# Escorna_CPU_1_01.net
KiCad netlist of a schematic drawn in EAGLE
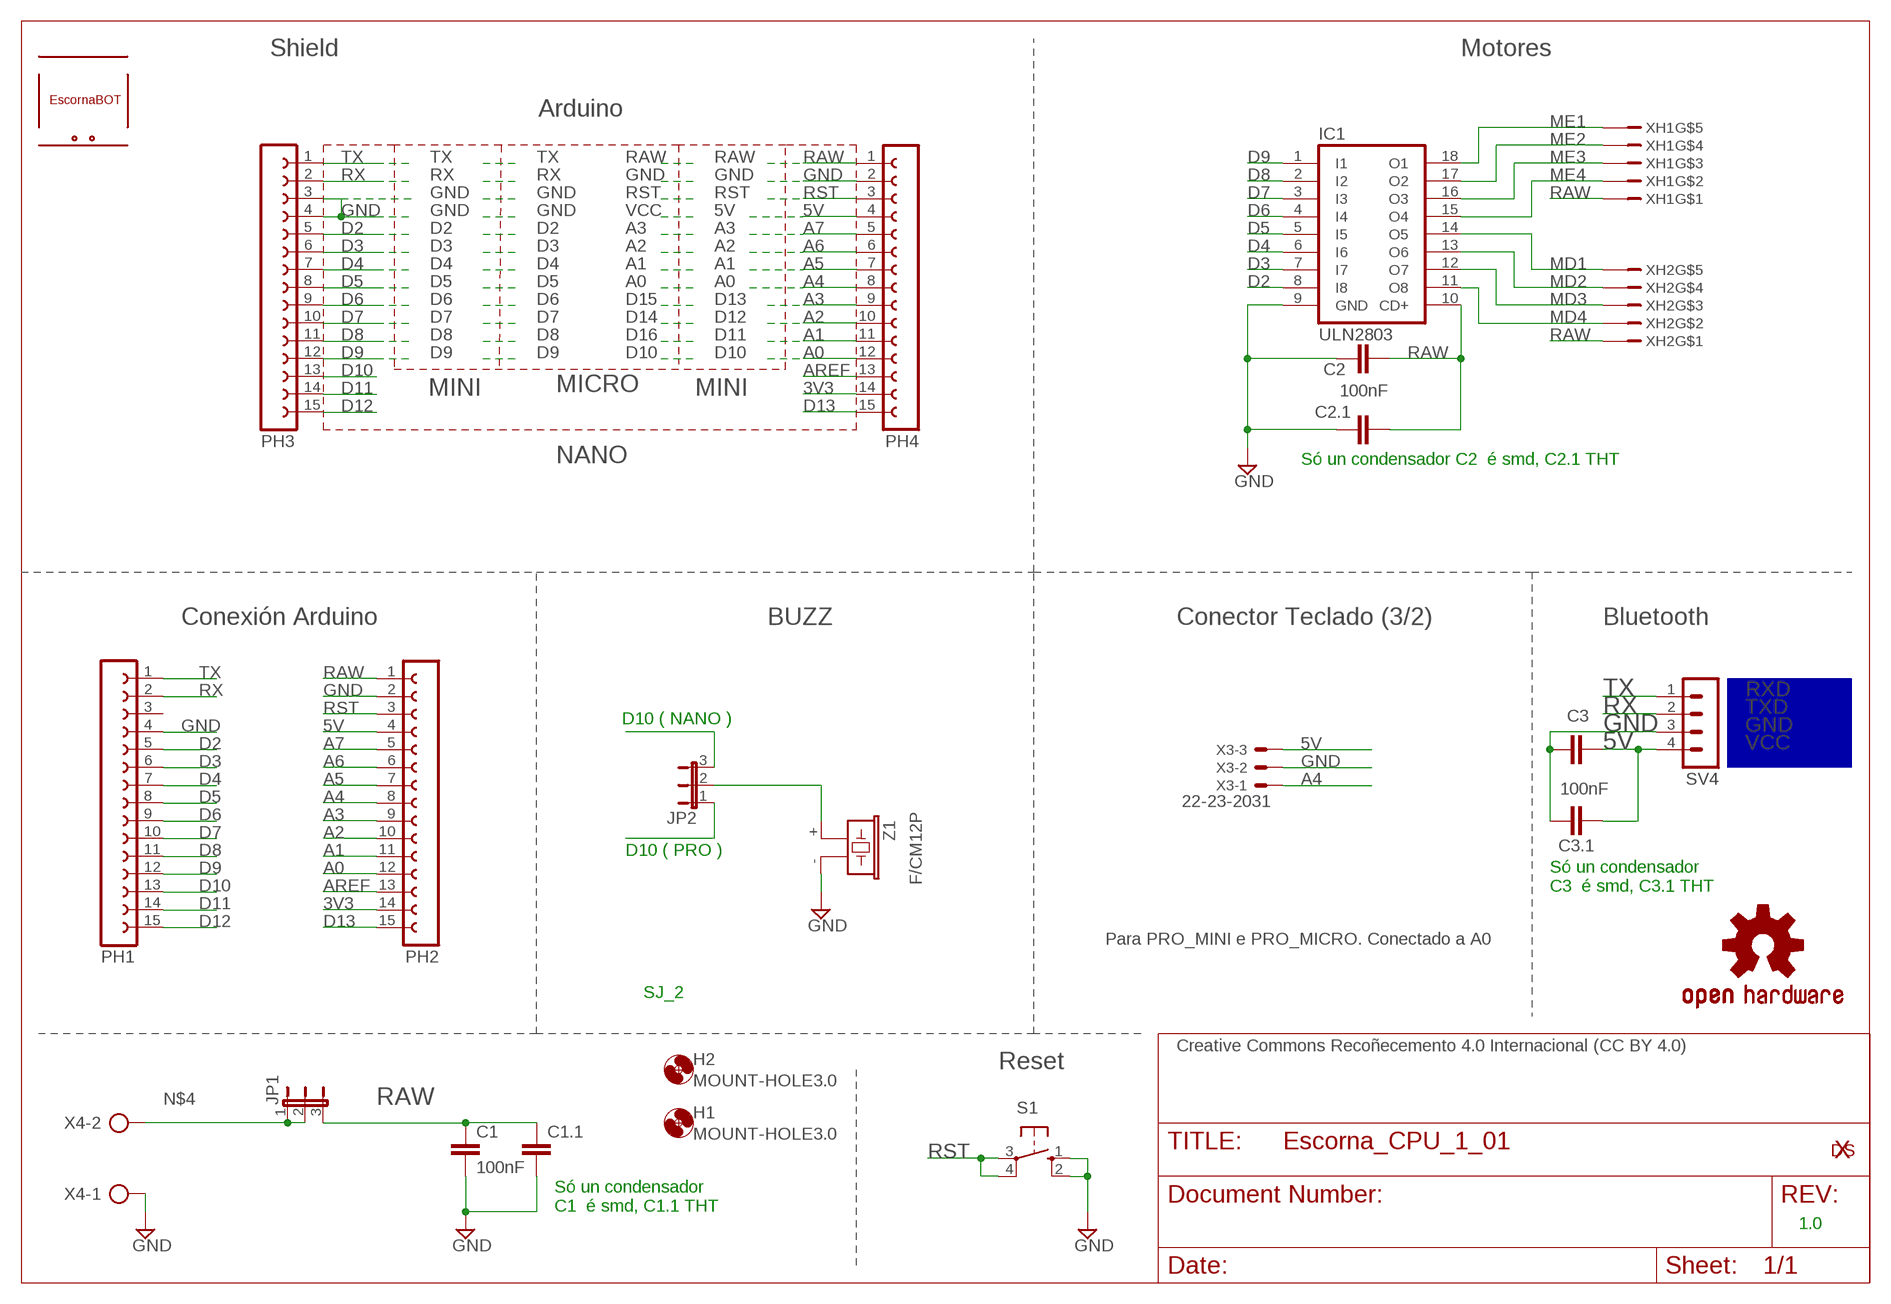
[diagram p0: schematic, sheet 1]

(export (version "E")
  (design (tool "Eeschema 10.0.6"))
  (components
    (comp (ref "C1")
      (value "100nF")
      (footprint "eagle-import:C1206")
      (libsource (lib "eagle-import") (part "C-EUC1206"))
    )
    (comp (ref "C1.1")
      (value "C-EU025-024X044")
      (footprint "eagle-import:C025-024X044")
      (libsource (lib "eagle-import") (part "C-EU025-024X044"))
    )
    (comp (ref "C2")
      (value "100nF")
      (footprint "eagle-import:C1206")
      (libsource (lib "eagle-import") (part "C-EUC1206"))
    )
    (comp (ref "C2.1")
      (value "C-EU025-024X044")
      (footprint "eagle-import:C025-024X044")
      (libsource (lib "eagle-import") (part "C-EU025-024X044"))
    )
    (comp (ref "C3")
      (value "100nF")
      (footprint "eagle-import:C1206")
      (libsource (lib "eagle-import") (part "C-EUC1206"))
    )
    (comp (ref "C3.1")
      (value "C-EU025-024X044")
      (footprint "eagle-import:C025-024X044")
      (libsource (lib "eagle-import") (part "C-EU025-024X044"))
    )
    (comp (ref "H1")
      (value "MOUNT-HOLE3.0")
      (footprint "eagle-import:3,0")
      (libsource (lib "eagle-import") (part "MOUNT-HOLE3.0"))
    )
    (comp (ref "H2")
      (value "MOUNT-HOLE3.0")
      (footprint "eagle-import:3,0")
      (libsource (lib "eagle-import") (part "MOUNT-HOLE3.0"))
    )
    (comp (ref "IC1")
      (value "ULN2803")
      (footprint "eagle-import:DIL18")
      (libsource (lib "eagle-import") (part "ULN2803A{dblquote}"))
    )
    (comp (ref "JP1")
      (value "JP2E")
      (footprint "eagle-import:JP2")
      (libsource (lib "eagle-import") (part "JP2E"))
    )
    (comp (ref "JP2")
      (value "JP2E")
      (footprint "eagle-import:JP2")
      (libsource (lib "eagle-import") (part "JP2E"))
    )
    (comp (ref "LOGO1")
      (value "OSHW-LOGOS")
      (footprint "eagle-import:OSHW-LOGO-S")
      (libsource (lib "eagle-import") (part "OSHW-LOGOS"))
    )
    (comp (ref "PH1")
      (value "FE15-1")
      (footprint "eagle-import:FE15")
      (libsource (lib "eagle-import") (part "FE15-1"))
    )
    (comp (ref "PH2")
      (value "FE15-1")
      (footprint "eagle-import:FE15")
      (libsource (lib "eagle-import") (part "FE15-1"))
    )
    (comp (ref "PH3")
      (value "FE15-1")
      (footprint "eagle-import:FE15")
      (libsource (lib "eagle-import") (part "FE15-1"))
    )
    (comp (ref "PH4")
      (value "FE15-1")
      (footprint "eagle-import:FE15")
      (libsource (lib "eagle-import") (part "FE15-1"))
    )
    (comp (ref "S1")
      (value "10-XX")
      (footprint "eagle-import:B3F-10XX")
      (fields (field (name "MPN") "B3F-1000"))
      (libsource (lib "eagle-import") (part "10-XX"))
    )
    (comp (ref "SV4")
      (value "MA04-1")
      (footprint "eagle-import:MA04-1")
      (libsource (lib "eagle-import") (part "MA04-1"))
    )
    (comp (ref "U$1")
      (value "ESCORNABOT")
      (footprint "eagle-import:ESCORNA_PEQUE")
      (libsource (lib "eagle-import") (part "ESCORNABOT"))
    )
    (comp (ref "U$6")
      (value "XDESIG")
      (footprint "eagle-import:XDESIG_CU")
      (libsource (lib "eagle-import") (part "XDESIG"))
    )
    (comp (ref "X3")
      (value "22-23-2031")
      (footprint "eagle-import:22-23-2031")
      (fields (field (name "MF") "MOLEX"))
      (libsource (lib "eagle-import") (part "22-23-2031"))
    )
    (comp (ref "X4")
      (value "AK500/2")
      (footprint "eagle-import:AK500_2")
      (libsource (lib "eagle-import") (part "AK500/2"))
    )
    (comp (ref "XH1")
      (value "B5B-XH-A")
      (footprint "eagle-import:B5B-XH-A")
      (libsource (lib "eagle-import") (part "B5B-XH-A"))
    )
    (comp (ref "XH2")
      (value "B5B-XH-A")
      (footprint "eagle-import:B5B-XH-A")
      (libsource (lib "eagle-import") (part "B5B-XH-A"))
    )
    (comp (ref "Z1")
      (value "F/CM12P")
      (footprint "eagle-import:F_CM12P")
      (libsource (lib "eagle-import") (part "F/CM12P"))
    )
  )
  (nets
    (net (code "1") (name "/3V3") (class "Default")
      (node (ref "PH2") (pin "14") (pinfunction "14_14") (pintype "passive"))
      (node (ref "PH4") (pin "14") (pinfunction "14_14") (pintype "passive"))
    )
    (net (code "2") (name "/5V") (class "Default")
      (node (ref "C3") (pin "2") (pinfunction "2_2") (pintype "passive"))
      (node (ref "C3.1") (pin "2") (pinfunction "2_2") (pintype "passive"))
      (node (ref "PH2") (pin "4") (pinfunction "4_4") (pintype "passive"))
      (node (ref "PH4") (pin "4") (pinfunction "4_4") (pintype "passive"))
      (node (ref "SV4") (pin "4") (pinfunction "4_4") (pintype "passive"))
      (node (ref "X3") (pin "3") (pinfunction "S_3") (pintype "passive"))
    )
    (net (code "3") (name "/A0") (class "Default")
      (node (ref "JP2") (pin "1") (pinfunction "1_1") (pintype "passive"))
      (node (ref "PH2") (pin "12") (pinfunction "12_12") (pintype "passive"))
      (node (ref "PH4") (pin "12") (pinfunction "12_12") (pintype "passive"))
    )
    (net (code "4") (name "/A1") (class "Default")
      (node (ref "PH2") (pin "11") (pinfunction "11_11") (pintype "passive"))
      (node (ref "PH4") (pin "11") (pinfunction "11_11") (pintype "passive"))
    )
    (net (code "5") (name "/A2") (class "Default")
      (node (ref "PH2") (pin "10") (pinfunction "10_10") (pintype "passive"))
      (node (ref "PH4") (pin "10") (pinfunction "10_10") (pintype "passive"))
    )
    (net (code "6") (name "/A3") (class "Default")
      (node (ref "PH2") (pin "9") (pinfunction "9_9") (pintype "passive"))
      (node (ref "PH4") (pin "9") (pinfunction "9_9") (pintype "passive"))
    )
    (net (code "7") (name "/A4") (class "Default")
      (node (ref "PH2") (pin "8") (pinfunction "8_8") (pintype "passive"))
      (node (ref "PH4") (pin "8") (pinfunction "8_8") (pintype "passive"))
      (node (ref "X3") (pin "1") (pinfunction "S_1") (pintype "passive"))
    )
    (net (code "8") (name "/A5") (class "Default")
      (node (ref "PH2") (pin "7") (pinfunction "7_7") (pintype "passive"))
      (node (ref "PH4") (pin "7") (pinfunction "7_7") (pintype "passive"))
    )
    (net (code "9") (name "/A6") (class "Default")
      (node (ref "PH2") (pin "6") (pinfunction "6_6") (pintype "passive"))
      (node (ref "PH4") (pin "6") (pinfunction "6_6") (pintype "passive"))
    )
    (net (code "10") (name "/A7") (class "Default")
      (node (ref "PH2") (pin "5") (pinfunction "5_5") (pintype "passive"))
      (node (ref "PH4") (pin "5") (pinfunction "5_5") (pintype "passive"))
    )
    (net (code "11") (name "/AREF") (class "Default")
      (node (ref "PH2") (pin "13") (pinfunction "13_13") (pintype "passive"))
      (node (ref "PH4") (pin "13") (pinfunction "13_13") (pintype "passive"))
    )
    (net (code "12") (name "/D2") (class "Default")
      (node (ref "IC1") (pin "8") (pinfunction "I8_8") (pintype "input"))
      (node (ref "PH1") (pin "5") (pinfunction "5_5") (pintype "passive"))
      (node (ref "PH3") (pin "5") (pinfunction "5_5") (pintype "passive"))
    )
    (net (code "13") (name "/D3") (class "Default")
      (node (ref "IC1") (pin "7") (pinfunction "I7_7") (pintype "input"))
      (node (ref "PH1") (pin "6") (pinfunction "6_6") (pintype "passive"))
      (node (ref "PH3") (pin "6") (pinfunction "6_6") (pintype "passive"))
    )
    (net (code "14") (name "/D4") (class "Default")
      (node (ref "IC1") (pin "6") (pinfunction "I6_6") (pintype "input"))
      (node (ref "PH1") (pin "7") (pinfunction "7_7") (pintype "passive"))
      (node (ref "PH3") (pin "7") (pinfunction "7_7") (pintype "passive"))
    )
    (net (code "15") (name "/D5") (class "Default")
      (node (ref "IC1") (pin "5") (pinfunction "I5_5") (pintype "input"))
      (node (ref "PH1") (pin "8") (pinfunction "8_8") (pintype "passive"))
      (node (ref "PH3") (pin "8") (pinfunction "8_8") (pintype "passive"))
    )
    (net (code "16") (name "/D6") (class "Default")
      (node (ref "IC1") (pin "4") (pinfunction "I4_4") (pintype "input"))
      (node (ref "PH1") (pin "9") (pinfunction "9_9") (pintype "passive"))
      (node (ref "PH3") (pin "9") (pinfunction "9_9") (pintype "passive"))
    )
    (net (code "17") (name "/D7") (class "Default")
      (node (ref "IC1") (pin "3") (pinfunction "I3_3") (pintype "input"))
      (node (ref "PH1") (pin "10") (pinfunction "10_10") (pintype "passive"))
      (node (ref "PH3") (pin "10") (pinfunction "10_10") (pintype "passive"))
    )
    (net (code "18") (name "/D8") (class "Default")
      (node (ref "IC1") (pin "2") (pinfunction "I2_2") (pintype "input"))
      (node (ref "PH1") (pin "11") (pinfunction "11_11") (pintype "passive"))
      (node (ref "PH3") (pin "11") (pinfunction "11_11") (pintype "passive"))
    )
    (net (code "19") (name "/D9") (class "Default")
      (node (ref "IC1") (pin "1") (pinfunction "I1_1") (pintype "input"))
      (node (ref "PH1") (pin "12") (pinfunction "12_12") (pintype "passive"))
      (node (ref "PH3") (pin "12") (pinfunction "12_12") (pintype "passive"))
    )
    (net (code "20") (name "/D10") (class "Default")
      (node (ref "JP2") (pin "3") (pinfunction "3_3") (pintype "passive"))
      (node (ref "PH1") (pin "13") (pinfunction "13_13") (pintype "passive"))
      (node (ref "PH3") (pin "13") (pinfunction "13_13") (pintype "passive"))
    )
    (net (code "21") (name "/D11") (class "Default")
      (node (ref "PH1") (pin "14") (pinfunction "14_14") (pintype "passive"))
      (node (ref "PH3") (pin "14") (pinfunction "14_14") (pintype "passive"))
    )
    (net (code "22") (name "/D12") (class "Default")
      (node (ref "PH1") (pin "15") (pinfunction "15_15") (pintype "passive"))
      (node (ref "PH3") (pin "15") (pinfunction "15_15") (pintype "passive"))
    )
    (net (code "23") (name "/D13") (class "Default")
      (node (ref "PH2") (pin "15") (pinfunction "15_15") (pintype "passive"))
      (node (ref "PH4") (pin "15") (pinfunction "15_15") (pintype "passive"))
    )
    (net (code "24") (name "/MD1") (class "Default")
      (node (ref "IC1") (pin "14") (pinfunction "O5_14") (pintype "open_collector"))
      (node (ref "XH2") (pin "P$5") (pinfunction "1_P$5") (pintype "passive"))
    )
    (net (code "25") (name "/MD2") (class "Default")
      (node (ref "IC1") (pin "13") (pinfunction "O6_13") (pintype "open_collector"))
      (node (ref "XH2") (pin "P$4") (pinfunction "1_P$4") (pintype "passive"))
    )
    (net (code "26") (name "/MD3") (class "Default")
      (node (ref "IC1") (pin "12") (pinfunction "O7_12") (pintype "open_collector"))
      (node (ref "XH2") (pin "P$3") (pinfunction "1_P$3") (pintype "passive"))
    )
    (net (code "27") (name "/MD4") (class "Default")
      (node (ref "IC1") (pin "11") (pinfunction "O8_11") (pintype "open_collector"))
      (node (ref "XH2") (pin "P$2") (pinfunction "1_P$2") (pintype "passive"))
    )
    (net (code "28") (name "/ME1") (class "Default")
      (node (ref "IC1") (pin "18") (pinfunction "O1_18") (pintype "open_collector"))
      (node (ref "XH1") (pin "P$5") (pinfunction "1_P$5") (pintype "passive"))
    )
    (net (code "29") (name "/ME2") (class "Default")
      (node (ref "IC1") (pin "17") (pinfunction "O2_17") (pintype "open_collector"))
      (node (ref "XH1") (pin "P$4") (pinfunction "1_P$4") (pintype "passive"))
    )
    (net (code "30") (name "/ME3") (class "Default")
      (node (ref "IC1") (pin "16") (pinfunction "O3_16") (pintype "open_collector"))
      (node (ref "XH1") (pin "P$3") (pinfunction "1_P$3") (pintype "passive"))
    )
    (net (code "31") (name "/ME4") (class "Default")
      (node (ref "IC1") (pin "15") (pinfunction "O4_15") (pintype "open_collector"))
      (node (ref "XH1") (pin "P$2") (pinfunction "1_P$2") (pintype "passive"))
    )
    (net (code "32") (name "/N$4") (class "Default")
      (node (ref "JP1") (pin "1") (pinfunction "1_1") (pintype "passive"))
      (node (ref "JP1") (pin "2") (pinfunction "2_2") (pintype "passive"))
      (node (ref "X4") (pin "2") (pinfunction "KL_2") (pintype "passive"))
    )
    (net (code "33") (name "/RAW") (class "Default")
      (node (ref "C1") (pin "1") (pinfunction "1_1") (pintype "passive"))
      (node (ref "C1.1") (pin "1") (pinfunction "1_1") (pintype "passive"))
      (node (ref "C2") (pin "2") (pinfunction "2_2") (pintype "passive"))
      (node (ref "C2.1") (pin "2") (pinfunction "2_2") (pintype "passive"))
      (node (ref "IC1") (pin "10") (pinfunction "CD+_10") (pintype "passive"))
      (node (ref "JP1") (pin "3") (pinfunction "3_3") (pintype "passive"))
      (node (ref "PH2") (pin "1") (pinfunction "1_1") (pintype "passive"))
      (node (ref "PH4") (pin "1") (pinfunction "1_1") (pintype "passive"))
      (node (ref "XH1") (pin "P$1") (pinfunction "1_P$1") (pintype "passive"))
      (node (ref "XH2") (pin "P$1") (pinfunction "1_P$1") (pintype "passive"))
    )
    (net (code "34") (name "/RST") (class "Default")
      (node (ref "PH2") (pin "3") (pinfunction "3_3") (pintype "passive"))
      (node (ref "PH4") (pin "3") (pinfunction "3_3") (pintype "passive"))
      (node (ref "S1") (pin "3") (pinfunction "P_3") (pintype "passive"))
      (node (ref "S1") (pin "4") (pinfunction "P1_4") (pintype "passive"))
    )
    (net (code "35") (name "/RX") (class "Default")
      (node (ref "PH1") (pin "2") (pinfunction "2_2") (pintype "passive"))
      (node (ref "PH3") (pin "2") (pinfunction "2_2") (pintype "passive"))
      (node (ref "SV4") (pin "2") (pinfunction "2_2") (pintype "passive"))
    )
    (net (code "36") (name "/TX") (class "Default")
      (node (ref "PH1") (pin "1") (pinfunction "1_1") (pintype "passive"))
      (node (ref "PH3") (pin "1") (pinfunction "1_1") (pintype "passive"))
      (node (ref "SV4") (pin "1") (pinfunction "1_1") (pintype "passive"))
    )
    (net (code "37") (name "GND") (class "Default")
      (node (ref "C1") (pin "2") (pinfunction "2_2") (pintype "passive"))
      (node (ref "C1.1") (pin "2") (pinfunction "2_2") (pintype "passive"))
      (node (ref "C2") (pin "1") (pinfunction "1_1") (pintype "passive"))
      (node (ref "C2.1") (pin "1") (pinfunction "1_1") (pintype "passive"))
      (node (ref "C3") (pin "1") (pinfunction "1_1") (pintype "passive"))
      (node (ref "C3.1") (pin "1") (pinfunction "1_1") (pintype "passive"))
      (node (ref "IC1") (pin "9") (pinfunction "GND_9") (pintype "power_in"))
      (node (ref "PH1") (pin "4") (pinfunction "4_4") (pintype "passive"))
      (node (ref "PH2") (pin "2") (pinfunction "2_2") (pintype "passive"))
      (node (ref "PH3") (pin "3") (pinfunction "3_3") (pintype "passive"))
      (node (ref "PH3") (pin "4") (pinfunction "4_4") (pintype "passive"))
      (node (ref "PH4") (pin "2") (pinfunction "2_2") (pintype "passive"))
      (node (ref "S1") (pin "1") (pinfunction "S_1") (pintype "passive"))
      (node (ref "S1") (pin "2") (pinfunction "S1_2") (pintype "passive"))
      (node (ref "SV4") (pin "3") (pinfunction "3_3") (pintype "passive"))
      (node (ref "X3") (pin "2") (pinfunction "S_2") (pintype "passive"))
      (node (ref "X4") (pin "1") (pinfunction "KL_1") (pintype "passive"))
      (node (ref "Z1") (pin "-") (pinfunction "2_-") (pintype "passive"))
    )
    (net (code "38") (name "Net-(Z1-1)") (class "Default")
      (node (ref "JP2") (pin "2") (pinfunction "2_2") (pintype "passive"))
      (node (ref "Z1") (pin "+") (pinfunction "1_+") (pintype "passive"))
    )
    (net (code "39") (name "unconnected-(PH1-Pad3)") (class "Default")
      (node (ref "PH1") (pin "3") (pinfunction "3_3") (pintype "passive"))
    )
  )
)
